# Connector.net
KiCad netlist of a schematic drawn in Altium Designer
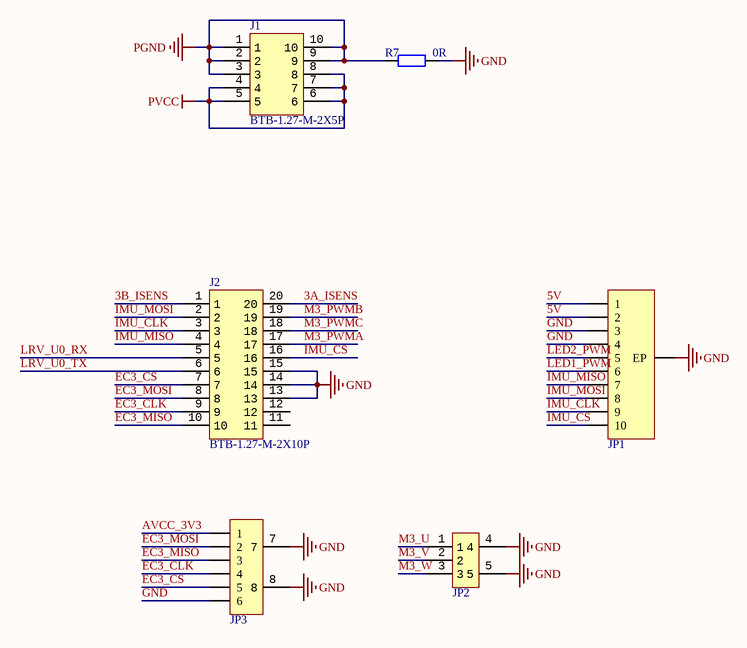
[diagram p0: Connector.SchDoc]

(export (version "E")
  (design (tool "Eeschema 10.0.6"))
  (components
    (comp (ref "J1")
      (value "BTB-1.27-M-2X5P")
      (footprint "1.27-M-2X5P")
      (libsource (lib "4.16 - BTB连接器 - 1.27") (part "M-2X5P"))
    )
    (comp (ref "J2")
      (value "BTB-1.27-M-2X10P")
      (footprint "1.27-M-2X10P")
      (libsource (lib "4.16 - BTB连接器 - 1.27") (part "M-2X10P"))
    )
    (comp (ref "JP1")
      (value "FPC1.0-10P")
      (footprint "FPC0.5 1H-WS-10P")
      (description "FPC连接器")
      (fields (field (name "版权归属") "源创客"))
      (libsource (lib "4.14 - FPC连接器") (part "FPC-10P"))
    )
    (comp (ref "JP2")
      (value "HDR-1X3")
      (footprint "GH 1.25-LS-3P")
      (description "3P接插件")
      (fields (field (name "版权归属") "源创客"))
      (libsource (lib "4.2   - 接插件-脚距1.25") (part "Header 3"))
    )
    (comp (ref "JP3")
      (value "HDR-1X6")
      (footprint "GH1.25-LS-6P")
      (description "6P接插件")
      (fields (field (name "版权归属") "源创客"))
      (libsource (lib "4.2   - 接插件-脚距1.25") (part "Header 6"))
    )
    (comp (ref "R7")
      (value "0R")
      (footprint "R 1206_L")
      (description "贴片电阻")
      (fields (field (name "版权归属") "源创客"))
      (libsource (lib "3.1   - 电阻-电容-电感") (part "R"))
    )
  )
  (nets
    (net (code "1") (name "/3A_ISENS") (class "Default")
      (node (ref "J2") (pin "20") (pinfunction "20_20") (pintype "passive"))
    )
    (net (code "2") (name "/3B_ISENS") (class "Default")
      (node (ref "J2") (pin "1") (pinfunction "1_1") (pintype "passive"))
    )
    (net (code "3") (name "/5V") (class "Default")
      (node (ref "JP1") (pin "1") (pinfunction "1_1") (pintype "passive"))
      (node (ref "JP1") (pin "2") (pinfunction "2_2") (pintype "passive"))
    )
    (net (code "4") (name "/AVCC_3V3") (class "Default")
      (node (ref "JP3") (pin "1") (pinfunction "1_1") (pintype "passive"))
    )
    (net (code "5") (name "/EC3_CLK") (class "Default")
      (node (ref "J2") (pin "9") (pinfunction "9_9") (pintype "passive"))
      (node (ref "JP3") (pin "4") (pinfunction "4_4") (pintype "passive"))
    )
    (net (code "6") (name "/EC3_CS") (class "Default")
      (node (ref "J2") (pin "7") (pinfunction "7_7") (pintype "passive"))
      (node (ref "JP3") (pin "5") (pinfunction "5_5") (pintype "passive"))
    )
    (net (code "7") (name "/EC3_MISO") (class "Default")
      (node (ref "J2") (pin "10") (pinfunction "10_10") (pintype "passive"))
      (node (ref "JP3") (pin "3") (pinfunction "3_3") (pintype "passive"))
    )
    (net (code "8") (name "/EC3_MOSI") (class "Default")
      (node (ref "J2") (pin "8") (pinfunction "8_8") (pintype "passive"))
      (node (ref "JP3") (pin "2") (pinfunction "2_2") (pintype "passive"))
    )
    (net (code "9") (name "/IMU_CLK") (class "Default")
      (node (ref "J2") (pin "3") (pinfunction "3_3") (pintype "passive"))
      (node (ref "JP1") (pin "9") (pinfunction "9_9") (pintype "passive"))
    )
    (net (code "10") (name "/IMU_CS") (class "Default")
      (node (ref "J2") (pin "16") (pinfunction "16_16") (pintype "passive"))
      (node (ref "JP1") (pin "10") (pinfunction "10_10") (pintype "passive"))
    )
    (net (code "11") (name "/IMU_MISO") (class "Default")
      (node (ref "J2") (pin "4") (pinfunction "4_4") (pintype "passive"))
      (node (ref "JP1") (pin "7") (pinfunction "7_7") (pintype "passive"))
    )
    (net (code "12") (name "/IMU_MOSI") (class "Default")
      (node (ref "J2") (pin "2") (pinfunction "2_2") (pintype "passive"))
      (node (ref "JP1") (pin "8") (pinfunction "8_8") (pintype "passive"))
    )
    (net (code "13") (name "/LED1_PWM") (class "Default")
      (node (ref "JP1") (pin "6") (pinfunction "6_6") (pintype "passive"))
    )
    (net (code "14") (name "/LED2_PWM") (class "Default")
      (node (ref "JP1") (pin "5") (pinfunction "5_5") (pintype "passive"))
    )
    (net (code "15") (name "/LRV_U0_RX") (class "Default")
      (node (ref "J2") (pin "5") (pinfunction "5_5") (pintype "passive"))
    )
    (net (code "16") (name "/LRV_U0_TX") (class "Default")
      (node (ref "J2") (pin "6") (pinfunction "6_6") (pintype "passive"))
    )
    (net (code "17") (name "/M3_PWMA") (class "Default")
      (node (ref "J2") (pin "17") (pinfunction "17_17") (pintype "passive"))
    )
    (net (code "18") (name "/M3_PWMB") (class "Default")
      (node (ref "J2") (pin "19") (pinfunction "19_19") (pintype "passive"))
    )
    (net (code "19") (name "/M3_PWMC") (class "Default")
      (node (ref "J2") (pin "18") (pinfunction "18_18") (pintype "passive"))
    )
    (net (code "20") (name "/M3_U") (class "Default")
      (node (ref "JP2") (pin "1") (pinfunction "1_1") (pintype "passive"))
    )
    (net (code "21") (name "/M3_V") (class "Default")
      (node (ref "JP2") (pin "2") (pinfunction "2_2") (pintype "passive"))
    )
    (net (code "22") (name "/M3_W") (class "Default")
      (node (ref "JP2") (pin "3") (pinfunction "3_3") (pintype "passive"))
    )
    (net (code "23") (name "GND") (class "Default")
      (node (ref "J2") (pin "13") (pinfunction "13_13") (pintype "passive"))
      (node (ref "J2") (pin "14") (pinfunction "14_14") (pintype "passive"))
      (node (ref "J2") (pin "15") (pinfunction "15_15") (pintype "passive"))
      (node (ref "JP1") (pin "0") (pinfunction "EP_0") (pintype "passive"))
      (node (ref "JP1") (pin "3") (pinfunction "3_3") (pintype "passive"))
      (node (ref "JP1") (pin "4") (pinfunction "4_4") (pintype "passive"))
      (node (ref "JP2") (pin "4") (pinfunction "4_4") (pintype "passive"))
      (node (ref "JP2") (pin "5") (pinfunction "5_5") (pintype "passive"))
      (node (ref "JP3") (pin "6") (pinfunction "6_6") (pintype "passive"))
      (node (ref "JP3") (pin "7") (pinfunction "7_7") (pintype "passive"))
      (node (ref "JP3") (pin "8") (pinfunction "8_8") (pintype "passive"))
      (node (ref "R7") (pin "2") (pinfunction "2_2") (pintype "passive"))
    )
    (net (code "24") (name "PGND") (class "Default")
      (node (ref "J1") (pin "1") (pinfunction "1_1") (pintype "passive"))
      (node (ref "J1") (pin "10") (pinfunction "10_10") (pintype "passive"))
      (node (ref "J1") (pin "2") (pinfunction "2_2") (pintype "passive"))
      (node (ref "J1") (pin "3") (pinfunction "3_3") (pintype "passive"))
      (node (ref "J1") (pin "9") (pinfunction "9_9") (pintype "passive"))
      (node (ref "R7") (pin "1") (pinfunction "1_1") (pintype "passive"))
    )
    (net (code "25") (name "PVCC") (class "Default")
      (node (ref "J1") (pin "4") (pinfunction "4_4") (pintype "passive"))
      (node (ref "J1") (pin "5") (pinfunction "5_5") (pintype "passive"))
      (node (ref "J1") (pin "6") (pinfunction "6_6") (pintype "passive"))
      (node (ref "J1") (pin "7") (pinfunction "7_7") (pintype "passive"))
      (node (ref "J1") (pin "8") (pinfunction "8_8") (pintype "passive"))
    )
    (net (code "26") (name "unconnected-(J2-Pad11)") (class "Default")
      (node (ref "J2") (pin "11") (pinfunction "11_11") (pintype "passive"))
    )
    (net (code "27") (name "unconnected-(J2-Pad12)") (class "Default")
      (node (ref "J2") (pin "12") (pinfunction "12_12") (pintype "passive"))
    )
  )
)
